# ManitoBoardL2.net
KiCad netlist of a schematic drawn in EAGLE
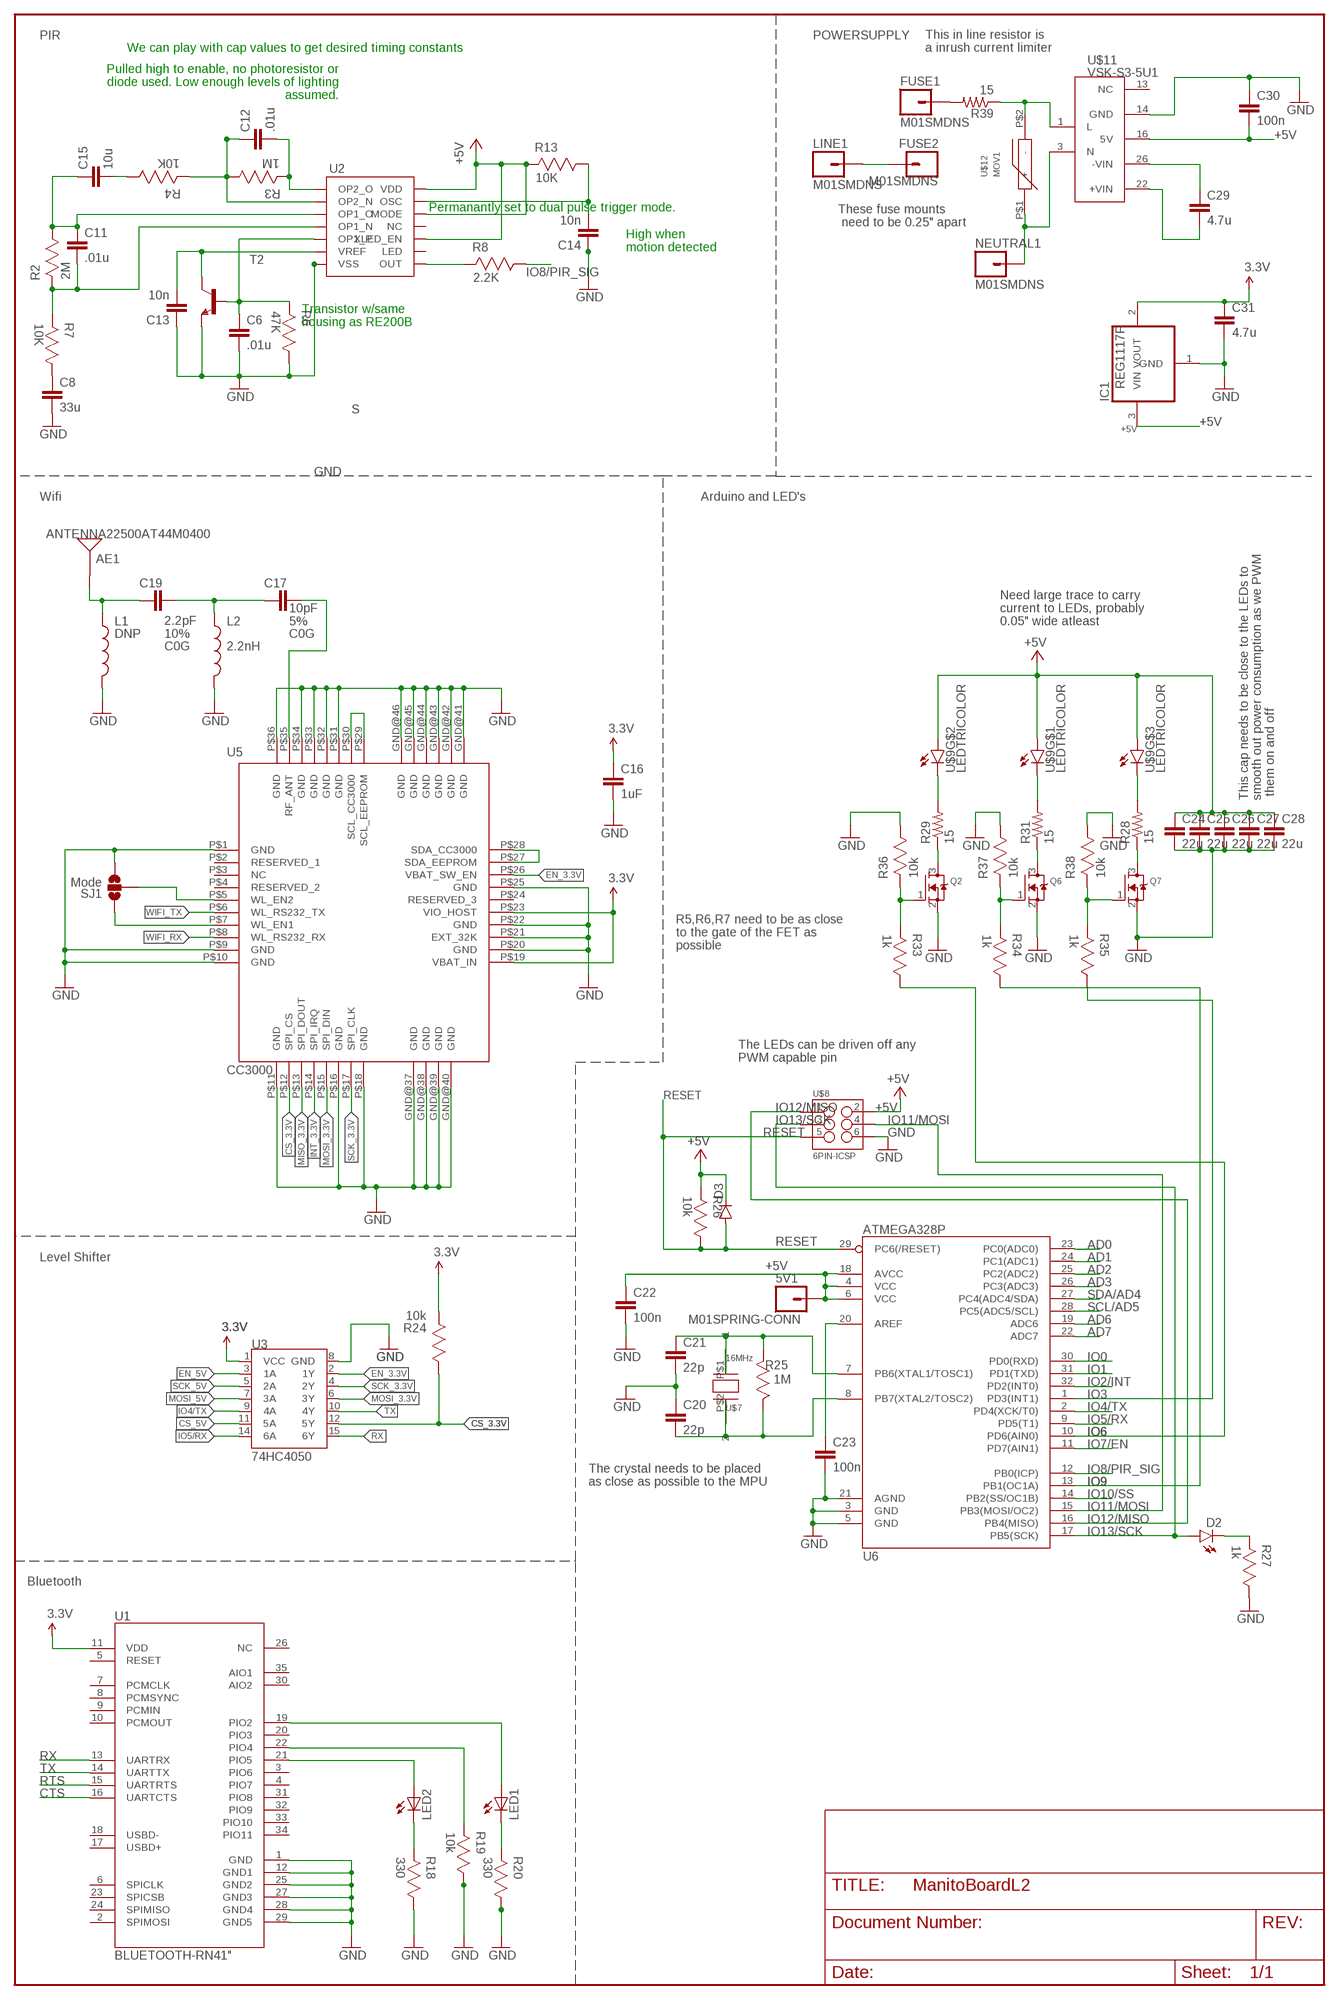
[diagram p0: schematic, sheet 1]

(export (version "E")
  (design (tool "Eeschema 10.0.6"))
  (components
    (comp (ref "5V1")
      (value "M01SPRING-CONN")
      (footprint "eagle-import:SPRING-CONNECTOR")
      (libsource (lib "eagle-import") (part "M01SPRING-CONN"))
    )
    (comp (ref "AE1")
      (value "ANTENNA22500AT44M0400")
      (footprint "eagle-import:ANTENNA-CHIP_2500AT44M0400")
      (libsource (lib "eagle-import") (part "ANTENNA22500AT44M0400"))
    )
    (comp (ref "C6")
      (value ".01u")
      (footprint "eagle-import:0805")
      (libsource (lib "eagle-import") (part "CAP0805"))
    )
    (comp (ref "C8")
      (value "33u")
      (footprint "eagle-import:0805")
      (libsource (lib "eagle-import") (part "CAP0805"))
    )
    (comp (ref "C11")
      (value ".01u")
      (footprint "eagle-import:0805")
      (libsource (lib "eagle-import") (part "CAP0805"))
    )
    (comp (ref "C12")
      (value ".01u")
      (footprint "eagle-import:0805")
      (libsource (lib "eagle-import") (part "CAP0805"))
    )
    (comp (ref "C13")
      (value "10n")
      (footprint "eagle-import:0805")
      (libsource (lib "eagle-import") (part "CAP0805"))
    )
    (comp (ref "C14")
      (value "10n")
      (footprint "eagle-import:0805")
      (libsource (lib "eagle-import") (part "CAP0805"))
    )
    (comp (ref "C15")
      (value "10u")
      (footprint "eagle-import:0805")
      (libsource (lib "eagle-import") (part "CAP0805"))
    )
    (comp (ref "C16")
      (value "1uF")
      (footprint "eagle-import:0805")
      (libsource (lib "eagle-import") (part "SparkFun-Capacitors_CAP0805"))
    )
    (comp (ref "C17")
      (value "10pF")
      (footprint "eagle-import:0603-CAP")
      (fields (field (name "COEFF") "C0G") (field (name "TOL") "5%"))
      (libsource (lib "eagle-import") (part "SparkFun-Capacitors_CAP0603-CAP"))
    )
    (comp (ref "C19")
      (value "2.2pF")
      (footprint "eagle-import:0603-CAP")
      (fields (field (name "COEFF") "C0G") (field (name "TOL") "10%"))
      (libsource (lib "eagle-import") (part "SparkFun-Capacitors_CAP0603-CAP"))
    )
    (comp (ref "C20")
      (value "22p")
      (footprint "eagle-import:0603-CAP")
      (libsource (lib "eagle-import") (part "CAP0603-CAP"))
    )
    (comp (ref "C21")
      (value "22p")
      (footprint "eagle-import:0603-CAP")
      (libsource (lib "eagle-import") (part "CAP0603-CAP"))
    )
    (comp (ref "C22")
      (value "100n")
      (footprint "eagle-import:0603-CAP")
      (libsource (lib "eagle-import") (part "CAP0603-CAP"))
    )
    (comp (ref "C23")
      (value "100n")
      (footprint "eagle-import:0603-CAP")
      (libsource (lib "eagle-import") (part "CAP0603-CAP"))
    )
    (comp (ref "C24")
      (value "22u")
      (footprint "eagle-import:0603-CAP")
      (libsource (lib "eagle-import") (part "CAP0603-CAP"))
    )
    (comp (ref "C25")
      (value "22u")
      (footprint "eagle-import:0603-CAP")
      (libsource (lib "eagle-import") (part "CAP0603-CAP"))
    )
    (comp (ref "C26")
      (value "22u")
      (footprint "eagle-import:0603-CAP")
      (libsource (lib "eagle-import") (part "CAP0603-CAP"))
    )
    (comp (ref "C27")
      (value "22u")
      (footprint "eagle-import:0603-CAP")
      (libsource (lib "eagle-import") (part "CAP0603-CAP"))
    )
    (comp (ref "C28")
      (value "22u")
      (footprint "eagle-import:0603-CAP")
      (libsource (lib "eagle-import") (part "CAP0603-CAP"))
    )
    (comp (ref "C29")
      (value "4.7u")
      (footprint "eagle-import:AXIAL-5MM")
      (libsource (lib "eagle-import") (part "CAP_"))
    )
    (comp (ref "C30")
      (value "100n")
      (footprint "eagle-import:0603-CAP")
      (libsource (lib "eagle-import") (part "CAP0603-CAP"))
    )
    (comp (ref "C31")
      (value "4.7u")
      (footprint "eagle-import:0603-CAP")
      (libsource (lib "eagle-import") (part "CAP0603-CAP"))
    )
    (comp (ref "D2")
      (value "LED-YELLOW0603")
      (footprint "eagle-import:LED-0603")
      (libsource (lib "eagle-import") (part "LED-YELLOW0603"))
    )
    (comp (ref "D3")
      (value "DIODESOD123")
      (footprint "eagle-import:SOD-123")
      (libsource (lib "eagle-import") (part "DIODESOD123"))
    )
    (comp (ref "FUSE1")
      (value "M01SMDNS")
      (footprint "eagle-import:1X01NS")
      (libsource (lib "eagle-import") (part "M01SMDNS"))
    )
    (comp (ref "FUSE2")
      (value "M01SMDNS")
      (footprint "eagle-import:1X01NS")
      (libsource (lib "eagle-import") (part "M01SMDNS"))
    )
    (comp (ref "IC1")
      (value "REG1117F")
      (footprint "eagle-import:DD-3")
      (fields (field (name "MF") "TEXAS INSTRUMENTS") (field (name "MPN") "REG1117FAKTTT"))
      (libsource (lib "eagle-import") (part "REG1117F"))
    )
    (comp (ref "L1")
      (value "DNP")
      (footprint "eagle-import:0603")
      (libsource (lib "eagle-import") (part "INDUCTOR0603"))
    )
    (comp (ref "L2")
      (value "2.2nH")
      (footprint "eagle-import:0603")
      (libsource (lib "eagle-import") (part "INDUCTOR0603"))
    )
    (comp (ref "LED1")
      (value "LED_ESML0603")
      (footprint "eagle-import:LED_SML0603")
      (libsource (lib "eagle-import") (part "LED_ESML0603"))
    )
    (comp (ref "LED2")
      (value "LED_ESML0603")
      (footprint "eagle-import:LED_SML0603")
      (libsource (lib "eagle-import") (part "LED_ESML0603"))
    )
    (comp (ref "LINE1")
      (value "M01SMDNS")
      (footprint "eagle-import:1X01NS")
      (libsource (lib "eagle-import") (part "M01SMDNS"))
    )
    (comp (ref "NEUTRAL1")
      (value "M01SMDNS")
      (footprint "eagle-import:1X01NS")
      (libsource (lib "eagle-import") (part "M01SMDNS"))
    )
    (comp (ref "Q2")
      (value "MOSFET-NREFLOW")
      (footprint "eagle-import:SOT23")
      (libsource (lib "eagle-import") (part "MOSFET-NREFLOW"))
    )
    (comp (ref "Q6")
      (value "MOSFET-NREFLOW")
      (footprint "eagle-import:SOT23")
      (libsource (lib "eagle-import") (part "MOSFET-NREFLOW"))
    )
    (comp (ref "Q7")
      (value "MOSFET-NREFLOW")
      (footprint "eagle-import:SOT23")
      (libsource (lib "eagle-import") (part "MOSFET-NREFLOW"))
    )
    (comp (ref "R2")
      (value "2M")
      (footprint "eagle-import:0603RESISTOR")
      (fields (field (name "MPN") "CRCW06031K21FKEA") (field (name "TOLERANCE") "± 1.0 %"))
      (libsource (lib "eagle-import") (part "0603RESISTOR1"))
    )
    (comp (ref "R3")
      (value "1M")
      (footprint "eagle-import:0603RESISTOR")
      (fields (field (name "MPN") "CRCW06031K21FKEA") (field (name "TOLERANCE") "± 1.0 %"))
      (libsource (lib "eagle-import") (part "0603RESISTOR1"))
    )
    (comp (ref "R4")
      (value "10K")
      (footprint "eagle-import:0603RESISTOR")
      (fields (field (name "MPN") "CRCW06031K21FKEA") (field (name "TOLERANCE") "± 1.0 %"))
      (libsource (lib "eagle-import") (part "0603RESISTOR1"))
    )
    (comp (ref "R6")
      (value "47K")
      (footprint "eagle-import:0603RESISTOR")
      (fields (field (name "MPN") "CRCW06031K21FKEA") (field (name "TOLERANCE") "± 1.0 %"))
      (libsource (lib "eagle-import") (part "0603RESISTOR1"))
    )
    (comp (ref "R7")
      (value "10K")
      (footprint "eagle-import:0603RESISTOR")
      (fields (field (name "MPN") "CRCW06031K21FKEA") (field (name "TOLERANCE") "± 1.0 %"))
      (libsource (lib "eagle-import") (part "0603RESISTOR1"))
    )
    (comp (ref "R8")
      (value "2.2K")
      (footprint "eagle-import:0603RESISTOR")
      (fields (field (name "MPN") "CRCW06031K21FKEA") (field (name "TOLERANCE") "± 1.0 %"))
      (libsource (lib "eagle-import") (part "0603RESISTOR1"))
    )
    (comp (ref "R13")
      (value "10K")
      (footprint "eagle-import:0603RESISTOR")
      (fields (field (name "MPN") "CRCW06031K21FKEA") (field (name "TOLERANCE") "± 1.0 %"))
      (libsource (lib "eagle-import") (part "0603RESISTOR1"))
    )
    (comp (ref "R18")
      (value "330")
      (footprint "eagle-import:0603RESISTOR")
      (fields (field (name "MPN") "CRCW06031K21FKEA") (field (name "TOLERANCE") "± 1.0 %"))
      (libsource (lib "eagle-import") (part "0603RESISTOR1"))
    )
    (comp (ref "R19")
      (value "10k")
      (footprint "eagle-import:0603RESISTOR")
      (fields (field (name "MPN") "CRCW06031K21FKEA") (field (name "TOLERANCE") "± 1.0 %"))
      (libsource (lib "eagle-import") (part "0603RESISTOR1"))
    )
    (comp (ref "R20")
      (value "330")
      (footprint "eagle-import:0603RESISTOR")
      (fields (field (name "MPN") "CRCW06031K21FKEA") (field (name "TOLERANCE") "± 1.0 %"))
      (libsource (lib "eagle-import") (part "0603RESISTOR1"))
    )
    (comp (ref "R24")
      (value "10k")
      (footprint "eagle-import:0603RESISTOR")
      (fields (field (name "MPN") "CRCW06031K21FKEA") (field (name "TOLERANCE") "± 1.0 %"))
      (libsource (lib "eagle-import") (part "0603RESISTOR1"))
    )
    (comp (ref "R25")
      (value "1M")
      (footprint "eagle-import:0603RESISTOR")
      (fields (field (name "MPN") "CRCW06031K21FKEA") (field (name "TOLERANCE") "± 1.0 %"))
      (libsource (lib "eagle-import") (part "0603RESISTOR1"))
    )
    (comp (ref "R26")
      (value "10k")
      (footprint "eagle-import:0603RESISTOR")
      (fields (field (name "MPN") "CRCW06031K21FKEA") (field (name "TOLERANCE") "± 1.0 %"))
      (libsource (lib "eagle-import") (part "0603RESISTOR1"))
    )
    (comp (ref "R27")
      (value "1k")
      (footprint "eagle-import:0603RESISTOR")
      (fields (field (name "MPN") "CRCW06031K21FKEA") (field (name "TOLERANCE") "± 1.0 %"))
      (libsource (lib "eagle-import") (part "0603RESISTOR1"))
    )
    (comp (ref "R28")
      (value "15")
      (footprint "eagle-import:AXIAL-0.6")
      (libsource (lib "eagle-import") (part "RESISTORPTH-1W"))
    )
    (comp (ref "R29")
      (value "15")
      (footprint "eagle-import:AXIAL-0.6")
      (libsource (lib "eagle-import") (part "RESISTORPTH-1W"))
    )
    (comp (ref "R31")
      (value "15")
      (footprint "eagle-import:AXIAL-0.6")
      (libsource (lib "eagle-import") (part "RESISTORPTH-1W"))
    )
    (comp (ref "R33")
      (value "1k")
      (footprint "eagle-import:0603RESISTOR")
      (fields (field (name "MPN") "CRCW06031K21FKEA") (field (name "TOLERANCE") "± 1.0 %"))
      (libsource (lib "eagle-import") (part "0603RESISTOR1"))
    )
    (comp (ref "R34")
      (value "1k")
      (footprint "eagle-import:0603RESISTOR")
      (fields (field (name "MPN") "CRCW06031K21FKEA") (field (name "TOLERANCE") "± 1.0 %"))
      (libsource (lib "eagle-import") (part "0603RESISTOR1"))
    )
    (comp (ref "R35")
      (value "1k")
      (footprint "eagle-import:0603RESISTOR")
      (fields (field (name "MPN") "CRCW06031K21FKEA") (field (name "TOLERANCE") "± 1.0 %"))
      (libsource (lib "eagle-import") (part "0603RESISTOR1"))
    )
    (comp (ref "R36")
      (value "10k")
      (footprint "eagle-import:0603RESISTOR")
      (fields (field (name "MPN") "CRCW06031K21FKEA") (field (name "TOLERANCE") "± 1.0 %"))
      (libsource (lib "eagle-import") (part "0603RESISTOR1"))
    )
    (comp (ref "R37")
      (value "10k")
      (footprint "eagle-import:0603RESISTOR")
      (fields (field (name "MPN") "CRCW06031K21FKEA") (field (name "TOLERANCE") "± 1.0 %"))
      (libsource (lib "eagle-import") (part "0603RESISTOR1"))
    )
    (comp (ref "R38")
      (value "10k")
      (footprint "eagle-import:0603RESISTOR")
      (fields (field (name "MPN") "CRCW06031K21FKEA") (field (name "TOLERANCE") "± 1.0 %"))
      (libsource (lib "eagle-import") (part "0603RESISTOR1"))
    )
    (comp (ref "R39")
      (value "15")
      (footprint "eagle-import:AXIAL-0.6")
      (libsource (lib "eagle-import") (part "RESISTORPTH-1W"))
    )
    (comp (ref "SJ1")
      (value "Mode")
      (footprint "eagle-import:SJ_3_PASTE1&2")
      (libsource (lib "eagle-import") (part "SOLDERJUMPER_2WAYPASTE1&2"))
    )
    (comp (ref "T2")
      (value "-NPN-TO5")
      (footprint "eagle-import:TO5")
      (libsource (lib "eagle-import") (part "-NPN-TO5"))
    )
    (comp (ref "U$7")
      (value "16MHz")
      (footprint "eagle-import:SMDCRYSTAL")
      (libsource (lib "eagle-import") (part "SMDCRYSTAL"))
    )
    (comp (ref "U$8")
      (value "6PIN-ICSP")
      (footprint "eagle-import:2X3-ICSP")
      (libsource (lib "eagle-import") (part "6PIN-ICSP"))
    )
    (comp (ref "U$9")
      (value "LEDTRICOLOR")
      (footprint "eagle-import:TRICOLORLED")
      (libsource (lib "eagle-import") (part "LEDTRICOLOR"))
    )
    (comp (ref "U$11")
      (value "VSK-S3-5U1")
      (footprint "eagle-import:VSK-S3-DCAC")
      (libsource (lib "eagle-import") (part "VSK-S3-5U1"))
    )
    (comp (ref "U$12")
      (value "MOV1")
      (footprint "eagle-import:MOV")
      (libsource (lib "eagle-import") (part "MOV1"))
    )
    (comp (ref "U1")
      (value "BLUETOOTH-RN41\"")
      (footprint "eagle-import:RN41")
      (libsource (lib "eagle-import") (part "BLUETOOTH-RN41{dblquote}"))
    )
    (comp (ref "U2")
      (value "NCS36000")
      (footprint "eagle-import:SO14")
      (libsource (lib "eagle-import") (part "NCS36000"))
    )
    (comp (ref "U3")
      (value "74HC4050")
      (footprint "eagle-import:SO016")
      (libsource (lib "eagle-import") (part "HEX_CONVERTER"))
    )
    (comp (ref "U5")
      (value "CC3000")
      (footprint "eagle-import:QFN-46_CC3000")
      (libsource (lib "eagle-import") (part "CC3000"))
    )
    (comp (ref "U6")
      (value "ATMEGA328P")
      (footprint "eagle-import:TQFP32-08")
      (libsource (lib "eagle-import") (part "ATMEGA328_SMT"))
    )
  )
  (nets
    (net (code "1") (name "+5V") (class "Default")
      (node (ref "5V1") (pin "P$2") (pinfunction "1_P$2") (pintype "passive"))
      (node (ref "C22") (pin "1") (pinfunction "1_1") (pintype "passive"))
      (node (ref "C24") (pin "1") (pinfunction "1_1") (pintype "passive"))
      (node (ref "C25") (pin "1") (pinfunction "1_1") (pintype "passive"))
      (node (ref "C26") (pin "1") (pinfunction "1_1") (pintype "passive"))
      (node (ref "C27") (pin "1") (pinfunction "1_1") (pintype "passive"))
      (node (ref "C28") (pin "1") (pinfunction "1_1") (pintype "passive"))
      (node (ref "C30") (pin "2") (pinfunction "2_2") (pintype "passive"))
      (node (ref "D3") (pin "C") (pinfunction "C_C") (pintype "passive"))
      (node (ref "IC1") (pin "3") (pinfunction "VIN_3") (pintype "input"))
      (node (ref "R13") (pin "2") (pinfunction "2_2") (pintype "passive"))
      (node (ref "R26") (pin "2") (pinfunction "2_2") (pintype "passive"))
      (node (ref "U$11") (pin "16") (pinfunction "5V_16") (pintype "bidirectional"))
      (node (ref "U$8") (pin "2") (pinfunction "+5V_2") (pintype "power_in"))
      (node (ref "U$9") (pin "A1") (pinfunction "A_A1") (pintype "passive"))
      (node (ref "U$9") (pin "A2") (pinfunction "A_A2") (pintype "passive"))
      (node (ref "U$9") (pin "A3") (pinfunction "A_A3") (pintype "passive"))
      (node (ref "U2") (pin "10") (pinfunction "XLED_EN_10") (pintype "bidirectional"))
      (node (ref "U2") (pin "12") (pinfunction "MODE_12") (pintype "bidirectional"))
      (node (ref "U2") (pin "14") (pinfunction "VDD_14") (pintype "power_in"))
      (node (ref "U6") (pin "18") (pinfunction "AVCC_18") (pintype "bidirectional"))
      (node (ref "U6") (pin "4") (pinfunction "VCC_4") (pintype "bidirectional"))
      (node (ref "U6") (pin "6") (pinfunction "VCC_6") (pintype "bidirectional"))
    )
    (net (code "2") (name "/AD0") (class "Default")
      (node (ref "U6") (pin "23") (pinfunction "PC0(ADC0)_23") (pintype "bidirectional"))
    )
    (net (code "3") (name "/AD1") (class "Default")
      (node (ref "U6") (pin "24") (pinfunction "PC1(ADC1)_24") (pintype "bidirectional"))
    )
    (net (code "4") (name "/AD2") (class "Default")
      (node (ref "U6") (pin "25") (pinfunction "PC2(ADC2)_25") (pintype "bidirectional"))
    )
    (net (code "5") (name "/AD3") (class "Default")
      (node (ref "U6") (pin "26") (pinfunction "PC3(ADC3)_26") (pintype "bidirectional"))
    )
    (net (code "6") (name "/AD6") (class "Default")
      (node (ref "U6") (pin "19") (pinfunction "ADC6_19") (pintype "bidirectional"))
    )
    (net (code "7") (name "/AD7") (class "Default")
      (node (ref "U6") (pin "22") (pinfunction "ADC7_22") (pintype "bidirectional"))
    )
    (net (code "8") (name "/CTS") (class "Default")
      (node (ref "U1") (pin "16") (pinfunction "UARTCTS_16") (pintype "bidirectional"))
    )
    (net (code "9") (name "/IO0") (class "Default")
      (node (ref "U6") (pin "30") (pinfunction "PD0(RXD)_30") (pintype "bidirectional"))
    )
    (net (code "10") (name "/IO1") (class "Default")
      (node (ref "U6") (pin "31") (pinfunction "PD1(TXD)_31") (pintype "bidirectional"))
    )
    (net (code "11") (name "/IO2{slash}INT") (class "Default")
      (node (ref "U6") (pin "32") (pinfunction "PD2(INT0)_32") (pintype "bidirectional"))
    )
    (net (code "12") (name "/IO3") (class "Default")
      (node (ref "R35") (pin "1") (pinfunction "1_1") (pintype "passive"))
      (node (ref "U6") (pin "1") (pinfunction "PD3(INT1)_1") (pintype "bidirectional"))
    )
    (net (code "13") (name "/IO6") (class "Default")
      (node (ref "R33") (pin "1") (pinfunction "1_1") (pintype "passive"))
      (node (ref "U6") (pin "10") (pinfunction "PD6(AIN0)_10") (pintype "bidirectional"))
    )
    (net (code "14") (name "/IO7{slash}EN") (class "Default")
      (node (ref "U6") (pin "11") (pinfunction "PD7(AIN1)_11") (pintype "bidirectional"))
    )
    (net (code "15") (name "/IO8{slash}PIR_SIG") (class "Default")
      (node (ref "R8") (pin "1") (pinfunction "1_1") (pintype "passive"))
      (node (ref "U6") (pin "12") (pinfunction "PB0(ICP)_12") (pintype "bidirectional"))
    )
    (net (code "16") (name "/IO9") (class "Default")
      (node (ref "R34") (pin "1") (pinfunction "1_1") (pintype "passive"))
      (node (ref "U6") (pin "13") (pinfunction "PB1(OC1A)_13") (pintype "bidirectional"))
    )
    (net (code "17") (name "/IO10{slash}SS") (class "Default")
      (node (ref "U6") (pin "14") (pinfunction "PB2(SS/OC1B)_14") (pintype "bidirectional"))
    )
    (net (code "18") (name "/IO11{slash}MOSI") (class "Default")
      (node (ref "U$8") (pin "4") (pinfunction "MOSI_4") (pintype "bidirectional"))
      (node (ref "U6") (pin "15") (pinfunction "PB3(MOSI/OC2)_15") (pintype "bidirectional"))
    )
    (net (code "19") (name "/IO12{slash}MISO") (class "Default")
      (node (ref "U$8") (pin "1") (pinfunction "MISO_1") (pintype "bidirectional"))
      (node (ref "U6") (pin "16") (pinfunction "PB4(MISO)_16") (pintype "bidirectional"))
    )
    (net (code "20") (name "/IO13{slash}SCK") (class "Default")
      (node (ref "D2") (pin "A") (pinfunction "A_A") (pintype "passive"))
      (node (ref "U$8") (pin "3") (pinfunction "SCK_3") (pintype "bidirectional"))
      (node (ref "U6") (pin "17") (pinfunction "PB5(SCK)_17") (pintype "bidirectional"))
    )
    (net (code "22") (name "/RESET") (class "Default")
      (node (ref "D3") (pin "A") (pinfunction "A_A") (pintype "passive"))
      (node (ref "R26") (pin "1") (pinfunction "1_1") (pintype "passive"))
      (node (ref "U$8") (pin "5") (pinfunction "RESET_5") (pintype "bidirectional"))
      (node (ref "U6") (pin "29") (pinfunction "PC6(/RESET)_29") (pintype "bidirectional"))
    )
    (net (code "23") (name "/RTS") (class "Default")
      (node (ref "U1") (pin "15") (pinfunction "UARTRTS_15") (pintype "bidirectional"))
    )
    (net (code "24") (name "/S") (class "Default")
      (node (ref "C6") (pin "1") (pinfunction "1_1") (pintype "passive"))
      (node (ref "R6") (pin "2") (pinfunction "2_2") (pintype "passive"))
      (node (ref "T2") (pin "2") (pinfunction "B_2") (pintype "passive"))
      (node (ref "U2") (pin "5") (pinfunction "OP1_P_5") (pintype "bidirectional"))
    )
    (net (code "25") (name "/SCL{slash}AD5") (class "Default")
      (node (ref "U6") (pin "28") (pinfunction "PC5(ADC5/SCL)_28") (pintype "bidirectional"))
    )
    (net (code "26") (name "/SDA{slash}AD4") (class "Default")
      (node (ref "U6") (pin "27") (pinfunction "PC4(ADC4/SDA)_27") (pintype "bidirectional"))
    )
    (net (code "27") (name "3.3V") (class "Default")
      (node (ref "C16") (pin "1") (pinfunction "1_1") (pintype "passive"))
      (node (ref "C31") (pin "1") (pinfunction "1_1") (pintype "passive"))
      (node (ref "IC1") (pin "2") (pinfunction "VOUT_2") (pintype "output"))
      (node (ref "R24") (pin "2") (pinfunction "2_2") (pintype "passive"))
      (node (ref "U1") (pin "11") (pinfunction "VDD_11") (pintype "bidirectional"))
      (node (ref "U3") (pin "1") (pinfunction "VCC_1") (pintype "bidirectional"))
      (node (ref "U5") (pin "P$19") (pinfunction "VBAT_IN_P$19") (pintype "bidirectional"))
      (node (ref "U5") (pin "P$23") (pinfunction "VIO_HOST_P$23") (pintype "bidirectional"))
    )
    (net (code "28") (name "CS_3.3V") (class "Default")
      (node (ref "R24") (pin "1") (pinfunction "1_1") (pintype "passive"))
      (node (ref "U3") (pin "12") (pinfunction "5Y_12") (pintype "bidirectional"))
      (node (ref "U5") (pin "P$12") (pinfunction "SPI_CS_P$12") (pintype "bidirectional"))
    )
    (net (code "29") (name "CS_5V") (class "Default")
      (node (ref "U3") (pin "11") (pinfunction "5A_11") (pintype "bidirectional"))
    )
    (net (code "30") (name "EN_3.3V") (class "Default")
      (node (ref "U3") (pin "2") (pinfunction "1Y_2") (pintype "bidirectional"))
      (node (ref "U5") (pin "P$26") (pinfunction "VBAT_SW_EN_P$26") (pintype "bidirectional"))
    )
    (net (code "31") (name "EN_5V") (class "Default")
      (node (ref "U3") (pin "3") (pinfunction "1A_3") (pintype "bidirectional"))
    )
    (net (code "32") (name "GND") (class "Default")
      (node (ref "C13") (pin "1") (pinfunction "1_1") (pintype "passive"))
      (node (ref "C14") (pin "1") (pinfunction "1_1") (pintype "passive"))
      (node (ref "C16") (pin "2") (pinfunction "2_2") (pintype "passive"))
      (node (ref "C20") (pin "1") (pinfunction "1_1") (pintype "passive"))
      (node (ref "C21") (pin "2") (pinfunction "2_2") (pintype "passive"))
      (node (ref "C22") (pin "2") (pinfunction "2_2") (pintype "passive"))
      (node (ref "C23") (pin "2") (pinfunction "2_2") (pintype "passive"))
      (node (ref "C24") (pin "2") (pinfunction "2_2") (pintype "passive"))
      (node (ref "C25") (pin "2") (pinfunction "2_2") (pintype "passive"))
      (node (ref "C26") (pin "2") (pinfunction "2_2") (pintype "passive"))
      (node (ref "C27") (pin "2") (pinfunction "2_2") (pintype "passive"))
      (node (ref "C28") (pin "2") (pinfunction "2_2") (pintype "passive"))
      (node (ref "C30") (pin "1") (pinfunction "1_1") (pintype "passive"))
      (node (ref "C31") (pin "2") (pinfunction "2_2") (pintype "passive"))
      (node (ref "C6") (pin "2") (pinfunction "2_2") (pintype "passive"))
      (node (ref "C8") (pin "2") (pinfunction "2_2") (pintype "passive"))
      (node (ref "IC1") (pin "1") (pinfunction "GND_1") (pintype "power_in"))
      (node (ref "L1") (pin "2") (pinfunction "2_2") (pintype "passive"))
      (node (ref "L2") (pin "2") (pinfunction "2_2") (pintype "passive"))
      (node (ref "Q2") (pin "2") (pinfunction "S_2") (pintype "bidirectional"))
      (node (ref "Q6") (pin "2") (pinfunction "S_2") (pintype "bidirectional"))
      (node (ref "Q7") (pin "2") (pinfunction "S_2") (pintype "bidirectional"))
      (node (ref "R18") (pin "1") (pinfunction "1_1") (pintype "passive"))
      (node (ref "R19") (pin "1") (pinfunction "1_1") (pintype "passive"))
      (node (ref "R20") (pin "1") (pinfunction "1_1") (pintype "passive"))
      (node (ref "R27") (pin "1") (pinfunction "1_1") (pintype "passive"))
      (node (ref "R36") (pin "1") (pinfunction "1_1") (pintype "passive"))
      (node (ref "R37") (pin "1") (pinfunction "1_1") (pintype "passive"))
      (node (ref "R38") (pin "1") (pinfunction "1_1") (pintype "passive"))
      (node (ref "R6") (pin "1") (pinfunction "1_1") (pintype "passive"))
      (node (ref "SJ1") (pin "3") (pinfunction "3_3") (pintype "passive"))
      (node (ref "T2") (pin "1") (pinfunction "E_1") (pintype "passive"))
      (node (ref "U$11") (pin "14") (pinfunction "GND_14") (pintype "bidirectional"))
      (node (ref "U$8") (pin "6") (pinfunction "GND_6") (pintype "power_in"))
      (node (ref "U1") (pin "1") (pinfunction "GND_1") (pintype "bidirectional"))
      (node (ref "U1") (pin "12") (pinfunction "GND1_12") (pintype "bidirectional"))
      (node (ref "U1") (pin "25") (pinfunction "GND2_25") (pintype "bidirectional"))
      (node (ref "U1") (pin "27") (pinfunction "GND3_27") (pintype "bidirectional"))
      (node (ref "U1") (pin "28") (pinfunction "GND4_28") (pintype "bidirectional"))
      (node (ref "U1") (pin "29") (pinfunction "GND5_29") (pintype "bidirectional"))
      (node (ref "U2") (pin "7") (pinfunction "VSS_7") (pintype "power_in"))
      (node (ref "U3") (pin "8") (pinfunction "GND_8") (pintype "bidirectional"))
      (node (ref "U5") (pin "GND@37") (pinfunction "GND_GND@37") (pintype "bidirectional"))
      (node (ref "U5") (pin "GND@38") (pinfunction "GND_GND@38") (pintype "bidirectional"))
      (node (ref "U5") (pin "GND@39") (pinfunction "GND_GND@39") (pintype "bidirectional"))
      (node (ref "U5") (pin "GND@40") (pinfunction "GND_GND@40") (pintype "bidirectional"))
      (node (ref "U5") (pin "GND@41") (pinfunction "GND_GND@41") (pintype "bidirectional"))
      (node (ref "U5") (pin "GND@42") (pinfunction "GND_GND@42") (pintype "bidirectional"))
      (node (ref "U5") (pin "GND@43") (pinfunction "GND_GND@43") (pintype "bidirectional"))
      (node (ref "U5") (pin "GND@44") (pinfunction "GND_GND@44") (pintype "bidirectional"))
      (node (ref "U5") (pin "GND@45") (pinfunction "GND_GND@45") (pintype "bidirectional"))
      (node (ref "U5") (pin "GND@46") (pinfunction "GND_GND@46") (pintype "bidirectional"))
      (node (ref "U5") (pin "P$1") (pinfunction "GND_P$1") (pintype "bidirectional"))
      (node (ref "U5") (pin "P$10") (pinfunction "GND_P$10") (pintype "bidirectional"))
      (node (ref "U5") (pin "P$11") (pinfunction "GND_P$11") (pintype "bidirectional"))
      (node (ref "U5") (pin "P$16") (pinfunction "GND_P$16") (pintype "bidirectional"))
      (node (ref "U5") (pin "P$18") (pinfunction "GND_P$18") (pintype "bidirectional"))
      (node (ref "U5") (pin "P$20") (pinfunction "GND_P$20") (pintype "bidirectional"))
      (node (ref "U5") (pin "P$21") (pinfunction "EXT_32K_P$21") (pintype "bidirectional"))
      (node (ref "U5") (pin "P$22") (pinfunction "GND_P$22") (pintype "bidirectional"))
      (node (ref "U5") (pin "P$25") (pinfunction "GND_P$25") (pintype "bidirectional"))
      (node (ref "U5") (pin "P$31") (pinfunction "GND_P$31") (pintype "bidirectional"))
      (node (ref "U5") (pin "P$32") (pinfunction "GND_P$32") (pintype "bidirectional"))
      (node (ref "U5") (pin "P$33") (pinfunction "GND_P$33") (pintype "bidirectional"))
      (node (ref "U5") (pin "P$34") (pinfunction "GND_P$34") (pintype "bidirectional"))
      (node (ref "U5") (pin "P$36") (pinfunction "GND_P$36") (pintype "bidirectional"))
      (node (ref "U5") (pin "P$9") (pinfunction "GND_P$9") (pintype "bidirectional"))
      (node (ref "U6") (pin "21") (pinfunction "AGND_21") (pintype "bidirectional"))
      (node (ref "U6") (pin "3") (pinfunction "GND_3") (pintype "bidirectional"))
      (node (ref "U6") (pin "5") (pinfunction "GND_5") (pintype "bidirectional"))
    )
    (net (code "33") (name "INT_3.3V") (class "Default")
      (node (ref "U5") (pin "P$14") (pinfunction "SPI_IRQ_P$14") (pintype "bidirectional"))
    )
    (net (code "34") (name "IO4{slash}TX") (class "Default")
      (node (ref "U3") (pin "9") (pinfunction "4A_9") (pintype "bidirectional"))
      (node (ref "U6") (pin "2") (pinfunction "PD4(XCK/T0)_2") (pintype "bidirectional"))
    )
    (net (code "35") (name "IO5{slash}RX") (class "Default")
      (node (ref "U3") (pin "14") (pinfunction "6A_14") (pintype "bidirectional"))
      (node (ref "U6") (pin "9") (pinfunction "PD5(T1)_9") (pintype "bidirectional"))
    )
    (net (code "36") (name "MISO_3.3V") (class "Default")
      (node (ref "U5") (pin "P$13") (pinfunction "SPI_DOUT_P$13") (pintype "bidirectional"))
    )
    (net (code "37") (name "MOSI_3.3V") (class "Default")
      (node (ref "U3") (pin "6") (pinfunction "3Y_6") (pintype "bidirectional"))
      (node (ref "U5") (pin "P$15") (pinfunction "SPI_DIN_P$15") (pintype "bidirectional"))
    )
    (net (code "38") (name "MOSI_5V") (class "Default")
      (node (ref "U3") (pin "7") (pinfunction "3A_7") (pintype "bidirectional"))
    )
    (net (code "39") (name "Net-(AE1-SIGNAL)") (class "Default")
      (node (ref "AE1") (pin "FEED") (pinfunction "SIGNAL_FEED") (pintype "bidirectional"))
      (node (ref "C19") (pin "1") (pinfunction "1_1") (pintype "passive"))
      (node (ref "L1") (pin "1") (pinfunction "1_1") (pintype "passive"))
    )
    (net (code "40") (name "Net-(C8-Pad1)") (class "Default")
      (node (ref "C8") (pin "1") (pinfunction "1_1") (pintype "passive"))
      (node (ref "R7") (pin "1") (pinfunction "1_1") (pintype "passive"))
    )
    (net (code "41") (name "Net-(C15-Pad2)") (class "Default")
      (node (ref "C15") (pin "2") (pinfunction "2_2") (pintype "passive"))
      (node (ref "R4") (pin "1") (pinfunction "1_1") (pintype "passive"))
    )
    (net (code "42") (name "Net-(C17-Pad1)") (class "Default")
      (node (ref "C17") (pin "1") (pinfunction "1_1") (pintype "passive"))
      (node (ref "C19") (pin "2") (pinfunction "2_2") (pintype "passive"))
      (node (ref "L2") (pin "1") (pinfunction "1_1") (pintype "passive"))
    )
    (net (code "43") (name "Net-(C29-1)") (class "Default")
      (node (ref "C29") (pin "P$1") (pinfunction "1_P$1") (pintype "passive"))
      (node (ref "U$11") (pin "26") (pinfunction "-VIN_26") (pintype "bidirectional"))
    )
    (net (code "44") (name "Net-(C29-2)") (class "Default")
      (node (ref "C29") (pin "P$2") (pinfunction "2_P$2") (pintype "passive"))
      (node (ref "U$11") (pin "22") (pinfunction "+VIN_22") (pintype "bidirectional"))
    )
    (net (code "45") (name "Net-(D2-PadC)") (class "Default")
      (node (ref "D2") (pin "C") (pinfunction "C_C") (pintype "passive"))
      (node (ref "R27") (pin "2") (pinfunction "2_2") (pintype "passive"))
    )
    (net (code "46") (name "Net-(FUSE2-Pad1)") (class "Default")
      (node (ref "FUSE2") (pin "1") (pinfunction "1_1") (pintype "passive"))
      (node (ref "LINE1") (pin "1") (pinfunction "1_1") (pintype "passive"))
    )
    (net (code "47") (name "Net-(LED1-PadC)") (class "Default")
      (node (ref "LED1") (pin "C") (pinfunction "C_C") (pintype "passive"))
      (node (ref "R20") (pin "2") (pinfunction "2_2") (pintype "passive"))
    )
    (net (code "48") (name "Net-(LED2-PadC)") (class "Default")
      (node (ref "LED2") (pin "C") (pinfunction "C_C") (pintype "passive"))
      (node (ref "R18") (pin "2") (pinfunction "2_2") (pintype "passive"))
    )
    (net (code "49") (name "Net-(Q2-D)") (class "Default")
      (node (ref "Q2") (pin "3") (pinfunction "D_3") (pintype "bidirectional"))
      (node (ref "R29") (pin "P$1") (pinfunction "1_P$1") (pintype "passive"))
    )
    (net (code "50") (name "Net-(Q2-G)") (class "Default")
      (node (ref "Q2") (pin "1") (pinfunction "G_1") (pintype "bidirectional"))
      (node (ref "R33") (pin "2") (pinfunction "2_2") (pintype "passive"))
      (node (ref "R36") (pin "2") (pinfunction "2_2") (pintype "passive"))
    )
    (net (code "51") (name "Net-(Q6-D)") (class "Default")
      (node (ref "Q6") (pin "3") (pinfunction "D_3") (pintype "bidirectional"))
      (node (ref "R31") (pin "P$1") (pinfunction "1_P$1") (pintype "passive"))
    )
    (net (code "52") (name "Net-(Q6-G)") (class "Default")
      (node (ref "Q6") (pin "1") (pinfunction "G_1") (pintype "bidirectional"))
      (node (ref "R34") (pin "2") (pinfunction "2_2") (pintype "passive"))
      (node (ref "R37") (pin "2") (pinfunction "2_2") (pintype "passive"))
    )
    (net (code "53") (name "Net-(Q7-D)") (class "Default")
      (node (ref "Q7") (pin "3") (pinfunction "D_3") (pintype "bidirectional"))
      (node (ref "R28") (pin "P$1") (pinfunction "1_P$1") (pintype "passive"))
    )
    (net (code "54") (name "Net-(Q7-G)") (class "Default")
      (node (ref "Q7") (pin "1") (pinfunction "G_1") (pintype "bidirectional"))
      (node (ref "R35") (pin "2") (pinfunction "2_2") (pintype "passive"))
      (node (ref "R38") (pin "2") (pinfunction "2_2") (pintype "passive"))
    )
    (net (code "55") (name "Net-(R28-2)") (class "Default")
      (node (ref "R28") (pin "P$2") (pinfunction "2_P$2") (pintype "passive"))
      (node (ref "U$9") (pin "C3") (pinfunction "C_C3") (pintype "passive"))
    )
    (net (code "56") (name "Net-(R29-2)") (class "Default")
      (node (ref "R29") (pin "P$2") (pinfunction "2_P$2") (pintype "passive"))
      (node (ref "U$9") (pin "C2") (pinfunction "C_C2") (pintype "passive"))
    )
    (net (code "57") (name "Net-(R31-2)") (class "Default")
      (node (ref "R31") (pin "P$2") (pinfunction "2_P$2") (pintype "passive"))
      (node (ref "U$9") (pin "C1") (pinfunction "C_C1") (pintype "passive"))
    )
    (net (code "58") (name "Net-(R39-1)") (class "Default")
      (node (ref "R39") (pin "P$1") (pinfunction "1_P$1") (pintype "passive"))
      (node (ref "U$11") (pin "1") (pinfunction "L_1") (pintype "bidirectional"))
      (node (ref "U$12") (pin "P$2") (pinfunction "-_P$2") (pintype "bidirectional"))
    )
    (net (code "59") (name "Net-(R39-2)") (class "Default")
      (node (ref "FUSE1") (pin "1") (pinfunction "1_1") (pintype "passive"))
      (node (ref "R39") (pin "P$2") (pinfunction "2_P$2") (pintype "passive"))
    )
    (net (code "60") (name "Net-(T2-C)") (class "Default")
      (node (ref "C13") (pin "2") (pinfunction "2_2") (pintype "passive"))
      (node (ref "T2") (pin "3") (pinfunction "C_3") (pintype "passive"))
      (node (ref "U2") (pin "6") (pinfunction "VREF_6") (pintype "power_in"))
    )
    (net (code "61") (name "Net-(U$7-1)") (class "Default")
      (node (ref "C21") (pin "1") (pinfunction "1_1") (pintype "passive"))
      (node (ref "R25") (pin "2") (pinfunction "2_2") (pintype "passive"))
      (node (ref "U$7") (pin "P$1") (pinfunction "1_P$1") (pintype "bidirectional"))
      (node (ref "U6") (pin "7") (pinfunction "PB6(XTAL1/TOSC1)_7") (pintype "bidirectional"))
    )
    (net (code "62") (name "Net-(U$7-2)") (class "Default")
      (node (ref "C20") (pin "2") (pinfunction "2_2") (pintype "passive"))
      (node (ref "R25") (pin "1") (pinfunction "1_1") (pintype "passive"))
      (node (ref "U$7") (pin "P$2") (pinfunction "2_P$2") (pintype "bidirectional"))
      (node (ref "U6") (pin "8") (pinfunction "PB7(XTAL2/TOSC2)_8") (pintype "bidirectional"))
    )
    (net (code "63") (name "Net-(U$11-N)") (class "Default")
      (node (ref "NEUTRAL1") (pin "1") (pinfunction "1_1") (pintype "passive"))
      (node (ref "U$11") (pin "3") (pinfunction "N_3") (pintype "bidirectional"))
      (node (ref "U$12") (pin "P$1") (pinfunction "+_P$1") (pintype "bidirectional"))
    )
    (net (code "64") (name "Net-(U1-PIO2)") (class "Default")
      (node (ref "LED1") (pin "A") (pinfunction "A_A") (pintype "passive"))
      (node (ref "U1") (pin "19") (pinfunction "PIO2_19") (pintype "bidirectional"))
    )
    (net (code "65") (name "Net-(U1-PIO4)") (class "Default")
      (node (ref "R19") (pin "2") (pinfunction "2_2") (pintype "passive"))
      (node (ref "U1") (pin "22") (pinfunction "PIO4_22") (pintype "bidirectional"))
    )
    (net (code "66") (name "Net-(U1-PIO5)") (class "Default")
      (node (ref "LED2") (pin "A") (pinfunction "A_A") (pintype "passive"))
      (node (ref "U1") (pin "21") (pinfunction "PIO5_21") (pintype "bidirectional"))
    )
    (net (code "67") (name "Net-(U2-OP1_N)") (class "Default")
      (node (ref "C11") (pin "2") (pinfunction "2_2") (pintype "passive"))
      (node (ref "R2") (pin "2") (pinfunction "2_2") (pintype "passive"))
      (node (ref "R7") (pin "2") (pinfunction "2_2") (pintype "passive"))
      (node (ref "U2") (pin "4") (pinfunction "OP1_N_4") (pintype "bidirectional"))
    )
    (net (code "68") (name "Net-(U2-OP1_O)") (class "Default")
      (node (ref "C11") (pin "1") (pinfunction "1_1") (pintype "passive"))
      (node (ref "C15") (pin "1") (pinfunction "1_1") (pintype "passive"))
      (node (ref "R2") (pin "1") (pinfunction "1_1") (pintype "passive"))
      (node (ref "U2") (pin "3") (pinfunction "OP1_O_3") (pintype "bidirectional"))
    )
    (net (code "69") (name "Net-(U2-OP2_N)") (class "Default")
      (node (ref "C12") (pin "1") (pinfunction "1_1") (pintype "passive"))
      (node (ref "R3") (pin "1") (pinfunction "1_1") (pintype "passive"))
      (node (ref "R4") (pin "2") (pinfunction "2_2") (pintype "passive"))
      (node (ref "U2") (pin "2") (pinfunction "OP2_N_2") (pintype "bidirectional"))
    )
    (net (code "70") (name "Net-(U2-OP2_O)") (class "Default")
      (node (ref "C12") (pin "2") (pinfunction "2_2") (pintype "passive"))
      (node (ref "R3") (pin "2") (pinfunction "2_2") (pintype "passive"))
      (node (ref "U2") (pin "1") (pinfunction "OP2_O_1") (pintype "bidirectional"))
    )
    (net (code "71") (name "Net-(U2-OSC)") (class "Default")
      (node (ref "C14") (pin "2") (pinfunction "2_2") (pintype "passive"))
      (node (ref "R13") (pin "1") (pinfunction "1_1") (pintype "passive"))
      (node (ref "U2") (pin "13") (pinfunction "OSC_13") (pintype "bidirectional"))
    )
    (net (code "72") (name "Net-(U2-OUT)") (class "Default")
      (node (ref "R8") (pin "2") (pinfunction "2_2") (pintype "passive"))
      (node (ref "U2") (pin "8") (pinfunction "OUT_8") (pintype "bidirectional"))
    )
    (net (code "73") (name "Net-(U5-RF_ANT)") (class "Default")
      (node (ref "C17") (pin "2") (pinfunction "2_2") (pintype "passive"))
      (node (ref "U5") (pin "P$35") (pinfunction "RF_ANT_P$35") (pintype "bidirectional"))
    )
    (net (code "74") (name "Net-(U5-SCL_CC3000)") (class "Default")
      (node (ref "U5") (pin "P$29") (pinfunction "SCL_EEPROM_P$29") (pintype "bidirectional"))
      (node (ref "U5") (pin "P$30") (pinfunction "SCL_CC3000_P$30") (pintype "bidirectional"))
    )
    (net (code "75") (name "Net-(U5-SDA_CC3000)") (class "Default")
      (node (ref "U5") (pin "P$27") (pinfunction "SDA_EEPROM_P$27") (pintype "bidirectional"))
      (node (ref "U5") (pin "P$28") (pinfunction "SDA_CC3000_P$28") (pintype "bidirectional"))
    )
    (net (code "76") (name "Net-(U5-WL_EN1)") (class "Default")
      (node (ref "SJ1") (pin "1") (pinfunction "1_1") (pintype "passive"))
      (node (ref "U5") (pin "P$7") (pinfunction "WL_EN1_P$7") (pintype "bidirectional"))
    )
    (net (code "77") (name "Net-(U5-WL_EN2)") (class "Default")
      (node (ref "SJ1") (pin "2") (pinfunction "2_2") (pintype "passive"))
      (node (ref "U5") (pin "P$5") (pinfunction "WL_EN2_P$5") (pintype "bidirectional"))
    )
    (net (code "78") (name "Net-(U6-AREF)") (class "Default")
      (node (ref "C23") (pin "1") (pinfunction "1_1") (pintype "passive"))
      (node (ref "U6") (pin "20") (pinfunction "AREF_20") (pintype "bidirectional"))
    )
    (net (code "79") (name "RX") (class "Default")
      (node (ref "U1") (pin "13") (pinfunction "UARTRX_13") (pintype "bidirectional"))
      (node (ref "U3") (pin "15") (pinfunction "6Y_15") (pintype "bidirectional"))
    )
    (net (code "80") (name "SCK_3.3V") (class "Default")
      (node (ref "U3") (pin "4") (pinfunction "2Y_4") (pintype "bidirectional"))
      (node (ref "U5") (pin "P$17") (pinfunction "SPI_CLK_P$17") (pintype "bidirectional"))
    )
    (net (code "81") (name "SCK_5V") (class "Default")
      (node (ref "U3") (pin "5") (pinfunction "2A_5") (pintype "bidirectional"))
    )
    (net (code "82") (name "TX") (class "Default")
      (node (ref "U1") (pin "14") (pinfunction "UARTTX_14") (pintype "bidirectional"))
      (node (ref "U3") (pin "10") (pinfunction "4Y_10") (pintype "bidirectional"))
    )
    (net (code "83") (name "WIFI_RX") (class "Default")
      (node (ref "U5") (pin "P$8") (pinfunction "WL_RS232_RX_P$8") (pintype "bidirectional"))
    )
    (net (code "84") (name "WIFI_TX") (class "Default")
      (node (ref "U5") (pin "P$6") (pinfunction "WL_RS232_TX_P$6") (pintype "bidirectional"))
    )
    (net (code "85") (name "unconnected-(U$11-NC-Pad13)") (class "Default")
      (node (ref "U$11") (pin "13") (pinfunction "NC_13") (pintype "no_connect"))
    )
    (net (code "86") (name "unconnected-(U1-AIO1-Pad35)") (class "Default")
      (node (ref "U1") (pin "35") (pinfunction "AIO1_35") (pintype "bidirectional"))
    )
    (net (code "87") (name "unconnected-(U1-AIO2-Pad30)") (class "Default")
      (node (ref "U1") (pin "30") (pinfunction "AIO2_30") (pintype "bidirectional"))
    )
    (net (code "88") (name "unconnected-(U1-NC-Pad26)") (class "Default")
      (node (ref "U1") (pin "26") (pinfunction "NC_26") (pintype "bidirectional"))
    )
    (net (code "89") (name "unconnected-(U1-PCMCLK-Pad7)") (class "Default")
      (node (ref "U1") (pin "7") (pinfunction "PCMCLK_7") (pintype "bidirectional"))
    )
    (net (code "90") (name "unconnected-(U1-PCMIN-Pad9)") (class "Default")
      (node (ref "U1") (pin "9") (pinfunction "PCMIN_9") (pintype "bidirectional"))
    )
    (net (code "91") (name "unconnected-(U1-PCMOUT-Pad10)") (class "Default")
      (node (ref "U1") (pin "10") (pinfunction "PCMOUT_10") (pintype "bidirectional"))
    )
    (net (code "92") (name "unconnected-(U1-PCMSYNC-Pad8)") (class "Default")
      (node (ref "U1") (pin "8") (pinfunction "PCMSYNC_8") (pintype "bidirectional"))
    )
    (net (code "93") (name "unconnected-(U1-PIO3-Pad20)") (class "Default")
      (node (ref "U1") (pin "20") (pinfunction "PIO3_20") (pintype "bidirectional"))
    )
    (net (code "94") (name "unconnected-(U1-PIO6-Pad3)") (class "Default")
      (node (ref "U1") (pin "3") (pinfunction "PIO6_3") (pintype "bidirectional"))
    )
    (net (code "95") (name "unconnected-(U1-PIO7-Pad4)") (class "Default")
      (node (ref "U1") (pin "4") (pinfunction "PIO7_4") (pintype "bidirectional"))
    )
    (net (code "96") (name "unconnected-(U1-PIO8-Pad31)") (class "Default")
      (node (ref "U1") (pin "31") (pinfunction "PIO8_31") (pintype "bidirectional"))
    )
    (net (code "97") (name "unconnected-(U1-PIO9-Pad32)") (class "Default")
      (node (ref "U1") (pin "32") (pinfunction "PIO9_32") (pintype "bidirectional"))
    )
    (net (code "98") (name "unconnected-(U1-PIO10-Pad33)") (class "Default")
      (node (ref "U1") (pin "33") (pinfunction "PIO10_33") (pintype "bidirectional"))
    )
    (net (code "99") (name "unconnected-(U1-PIO11-Pad34)") (class "Default")
      (node (ref "U1") (pin "34") (pinfunction "PIO11_34") (pintype "bidirectional"))
    )
    (net (code "100") (name "unconnected-(U1-RESET-Pad5)") (class "Default")
      (node (ref "U1") (pin "5") (pinfunction "RESET_5") (pintype "bidirectional"))
    )
    (net (code "101") (name "unconnected-(U1-SPICLK-Pad6)") (class "Default")
      (node (ref "U1") (pin "6") (pinfunction "SPICLK_6") (pintype "bidirectional"))
    )
    (net (code "102") (name "unconnected-(U1-SPICSB-Pad23)") (class "Default")
      (node (ref "U1") (pin "23") (pinfunction "SPICSB_23") (pintype "bidirectional"))
    )
    (net (code "103") (name "unconnected-(U1-SPIMISO-Pad24)") (class "Default")
      (node (ref "U1") (pin "24") (pinfunction "SPIMISO_24") (pintype "bidirectional"))
    )
    (net (code "104") (name "unconnected-(U1-SPIMOSI-Pad2)") (class "Default")
      (node (ref "U1") (pin "2") (pinfunction "SPIMOSI_2") (pintype "bidirectional"))
    )
    (net (code "105") (name "unconnected-(U1-USBD+-Pad17)") (class "Default")
      (node (ref "U1") (pin "17") (pinfunction "USBD+_17") (pintype "bidirectional"))
    )
    (net (code "106") (name "unconnected-(U1-USBD--Pad18)") (class "Default")
      (node (ref "U1") (pin "18") (pinfunction "USBD-_18") (pintype "bidirectional"))
    )
    (net (code "107") (name "unconnected-(U2-LED-Pad9)") (class "Default")
      (node (ref "U2") (pin "9") (pinfunction "LED_9") (pintype "bidirectional"))
    )
    (net (code "108") (name "unconnected-(U2-NC-Pad11)") (class "Default")
      (node (ref "U2") (pin "11") (pinfunction "NC_11") (pintype "bidirectional"))
    )
    (net (code "109") (name "unconnected-(U5-NC-PadP$3)") (class "Default")
      (node (ref "U5") (pin "P$3") (pinfunction "NC_P$3") (pintype "bidirectional"))
    )
    (net (code "110") (name "unconnected-(U5-RESERVED_1-PadP$2)") (class "Default")
      (node (ref "U5") (pin "P$2") (pinfunction "RESERVED_1_P$2") (pintype "bidirectional"))
    )
    (net (code "111") (name "unconnected-(U5-RESERVED_2-PadP$4)") (class "Default")
      (node (ref "U5") (pin "P$4") (pinfunction "RESERVED_2_P$4") (pintype "bidirectional"))
    )
    (net (code "112") (name "unconnected-(U5-RESERVED_3-PadP$24)") (class "Default")
      (node (ref "U5") (pin "P$24") (pinfunction "RESERVED_3_P$24") (pintype "bidirectional"))
    )
  )
)
